# schematic.net
KiCad netlist of a schematic drawn in EAGLE
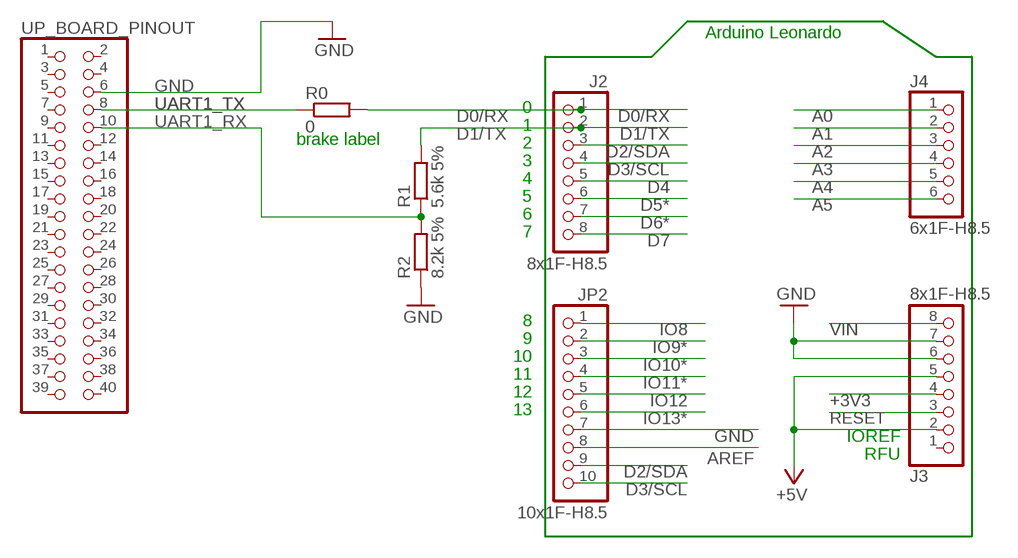
[diagram p0: schematic, sheet 1]

(export (version "E")
  (design (tool "Eeschema 10.0.6"))
  (components
    (comp (ref "J2")
      (value "8x1F-H8.5")
      (footprint "eagle-import:1X08")
      (libsource (lib "eagle-import") (part "PINHD-1X8"))
    )
    (comp (ref "J3")
      (value "8x1F-H8.5")
      (footprint "eagle-import:1X08")
      (libsource (lib "eagle-import") (part "PINHD-1X8"))
    )
    (comp (ref "J4")
      (value "6x1F-H8.5")
      (footprint "eagle-import:1X06")
      (libsource (lib "eagle-import") (part "PINHD-1X6"))
    )
    (comp (ref "JP2")
      (value "10x1F-H8.5")
      (footprint "eagle-import:1X10")
      (libsource (lib "eagle-import") (part "PINHD-1X10"))
    )
    (comp (ref "R0")
      (value "0")
      (footprint "eagle-import:0204V")
      (libsource (lib "eagle-import") (part "R-EU_0204/2V"))
    )
    (comp (ref "R1")
      (value "5.6k 5%")
      (footprint "eagle-import:0204V")
      (libsource (lib "eagle-import") (part "R-EU_0204/2V"))
    )
    (comp (ref "R2")
      (value "8.2k 5%")
      (footprint "eagle-import:0204V")
      (libsource (lib "eagle-import") (part "R-EU_0204/2V"))
    )
    (comp (ref "UP_BOARD_PINOUT")
      (value "PINHD-2X20")
      (footprint "eagle-import:2X20")
      (libsource (lib "eagle-import") (part "PINHD-2X20"))
    )
  )
  (nets
    (net (code "1") (name "+5V") (class "Default")
      (node (ref "J3") (pin "2") (pinfunction "2_2") (pintype "passive"))
      (node (ref "J3") (pin "5") (pinfunction "5_5") (pintype "passive"))
    )
    (net (code "2") (name "/+3V3") (class "Default")
      (node (ref "J3") (pin "4") (pinfunction "4_4") (pintype "passive"))
    )
    (net (code "3") (name "/A0") (class "Default")
      (node (ref "J4") (pin "1") (pinfunction "1_1") (pintype "passive"))
    )
    (net (code "4") (name "/A1") (class "Default")
      (node (ref "J4") (pin "2") (pinfunction "2_2") (pintype "passive"))
    )
    (net (code "5") (name "/A2") (class "Default")
      (node (ref "J4") (pin "3") (pinfunction "3_3") (pintype "passive"))
    )
    (net (code "6") (name "/A3") (class "Default")
      (node (ref "J4") (pin "4") (pinfunction "4_4") (pintype "passive"))
    )
    (net (code "7") (name "/A4") (class "Default")
      (node (ref "J4") (pin "5") (pinfunction "5_5") (pintype "passive"))
    )
    (net (code "8") (name "/A5") (class "Default")
      (node (ref "J4") (pin "6") (pinfunction "6_6") (pintype "passive"))
    )
    (net (code "9") (name "/AREF") (class "Default")
      (node (ref "JP2") (pin "8") (pinfunction "8_8") (pintype "passive"))
    )
    (net (code "10") (name "/D0{slash}RX") (class "Default")
      (node (ref "J2") (pin "1") (pinfunction "1_1") (pintype "passive"))
      (node (ref "R0") (pin "2") (pinfunction "2_2") (pintype "passive"))
    )
    (net (code "11") (name "/D1{slash}TX") (class "Default")
      (node (ref "J2") (pin "2") (pinfunction "2_2") (pintype "passive"))
      (node (ref "R1") (pin "2") (pinfunction "2_2") (pintype "passive"))
    )
    (net (code "12") (name "/D2{slash}SDA") (class "Default")
      (node (ref "J2") (pin "3") (pinfunction "3_3") (pintype "passive"))
      (node (ref "JP2") (pin "9") (pinfunction "9_9") (pintype "passive"))
    )
    (net (code "13") (name "/D3{slash}SCL") (class "Default")
      (node (ref "J2") (pin "4") (pinfunction "4_4") (pintype "passive"))
      (node (ref "JP2") (pin "10") (pinfunction "10_10") (pintype "passive"))
    )
    (net (code "14") (name "/D4") (class "Default")
      (node (ref "J2") (pin "5") (pinfunction "5_5") (pintype "passive"))
    )
    (net (code "15") (name "/D5*") (class "Default")
      (node (ref "J2") (pin "6") (pinfunction "6_6") (pintype "passive"))
    )
    (net (code "16") (name "/D6*") (class "Default")
      (node (ref "J2") (pin "7") (pinfunction "7_7") (pintype "passive"))
    )
    (net (code "17") (name "/D7") (class "Default")
      (node (ref "J2") (pin "8") (pinfunction "8_8") (pintype "passive"))
    )
    (net (code "18") (name "/IO8") (class "Default")
      (node (ref "JP2") (pin "1") (pinfunction "1_1") (pintype "passive"))
    )
    (net (code "19") (name "/IO9*") (class "Default")
      (node (ref "JP2") (pin "2") (pinfunction "2_2") (pintype "passive"))
    )
    (net (code "20") (name "/IO10*") (class "Default")
      (node (ref "JP2") (pin "3") (pinfunction "3_3") (pintype "passive"))
    )
    (net (code "21") (name "/IO11*") (class "Default")
      (node (ref "JP2") (pin "4") (pinfunction "4_4") (pintype "passive"))
    )
    (net (code "22") (name "/IO12") (class "Default")
      (node (ref "JP2") (pin "5") (pinfunction "5_5") (pintype "passive"))
    )
    (net (code "23") (name "/IO13*") (class "Default")
      (node (ref "JP2") (pin "6") (pinfunction "6_6") (pintype "passive"))
    )
    (net (code "24") (name "/RESET") (class "Default")
      (node (ref "J3") (pin "3") (pinfunction "3_3") (pintype "passive"))
    )
    (net (code "25") (name "/UART1_RX") (class "Default")
      (node (ref "R1") (pin "1") (pinfunction "1_1") (pintype "passive"))
      (node (ref "R2") (pin "2") (pinfunction "2_2") (pintype "passive"))
      (node (ref "UP_BOARD_PINOUT") (pin "10") (pinfunction "10_10") (pintype "passive"))
    )
    (net (code "26") (name "/UART1_TX") (class "Default")
      (node (ref "R0") (pin "1") (pinfunction "1_1") (pintype "passive"))
      (node (ref "UP_BOARD_PINOUT") (pin "8") (pinfunction "8_8") (pintype "passive"))
    )
    (net (code "27") (name "/VIN") (class "Default")
      (node (ref "J3") (pin "8") (pinfunction "8_8") (pintype "passive"))
    )
    (net (code "28") (name "GND") (class "Default")
      (node (ref "J3") (pin "6") (pinfunction "6_6") (pintype "passive"))
      (node (ref "J3") (pin "7") (pinfunction "7_7") (pintype "passive"))
      (node (ref "JP2") (pin "7") (pinfunction "7_7") (pintype "passive"))
      (node (ref "R2") (pin "1") (pinfunction "1_1") (pintype "passive"))
      (node (ref "UP_BOARD_PINOUT") (pin "6") (pinfunction "6_6") (pintype "passive"))
    )
    (net (code "29") (name "unconnected-(J3-Pad1)") (class "Default")
      (node (ref "J3") (pin "1") (pinfunction "1_1") (pintype "passive"))
    )
    (net (code "30") (name "unconnected-(UP_BOARD_PINOUT-Pad1)") (class "Default")
      (node (ref "UP_BOARD_PINOUT") (pin "1") (pinfunction "1_1") (pintype "passive"))
    )
    (net (code "31") (name "unconnected-(UP_BOARD_PINOUT-Pad2)") (class "Default")
      (node (ref "UP_BOARD_PINOUT") (pin "2") (pinfunction "2_2") (pintype "passive"))
    )
    (net (code "32") (name "unconnected-(UP_BOARD_PINOUT-Pad3)") (class "Default")
      (node (ref "UP_BOARD_PINOUT") (pin "3") (pinfunction "3_3") (pintype "passive"))
    )
    (net (code "33") (name "unconnected-(UP_BOARD_PINOUT-Pad4)") (class "Default")
      (node (ref "UP_BOARD_PINOUT") (pin "4") (pinfunction "4_4") (pintype "passive"))
    )
    (net (code "34") (name "unconnected-(UP_BOARD_PINOUT-Pad5)") (class "Default")
      (node (ref "UP_BOARD_PINOUT") (pin "5") (pinfunction "5_5") (pintype "passive"))
    )
    (net (code "35") (name "unconnected-(UP_BOARD_PINOUT-Pad7)") (class "Default")
      (node (ref "UP_BOARD_PINOUT") (pin "7") (pinfunction "7_7") (pintype "passive"))
    )
    (net (code "36") (name "unconnected-(UP_BOARD_PINOUT-Pad9)") (class "Default")
      (node (ref "UP_BOARD_PINOUT") (pin "9") (pinfunction "9_9") (pintype "passive"))
    )
    (net (code "37") (name "unconnected-(UP_BOARD_PINOUT-Pad11)") (class "Default")
      (node (ref "UP_BOARD_PINOUT") (pin "11") (pinfunction "11_11") (pintype "passive"))
    )
    (net (code "38") (name "unconnected-(UP_BOARD_PINOUT-Pad12)") (class "Default")
      (node (ref "UP_BOARD_PINOUT") (pin "12") (pinfunction "12_12") (pintype "passive"))
    )
    (net (code "39") (name "unconnected-(UP_BOARD_PINOUT-Pad13)") (class "Default")
      (node (ref "UP_BOARD_PINOUT") (pin "13") (pinfunction "13_13") (pintype "passive"))
    )
    (net (code "40") (name "unconnected-(UP_BOARD_PINOUT-Pad14)") (class "Default")
      (node (ref "UP_BOARD_PINOUT") (pin "14") (pinfunction "14_14") (pintype "passive"))
    )
    (net (code "41") (name "unconnected-(UP_BOARD_PINOUT-Pad15)") (class "Default")
      (node (ref "UP_BOARD_PINOUT") (pin "15") (pinfunction "15_15") (pintype "passive"))
    )
    (net (code "42") (name "unconnected-(UP_BOARD_PINOUT-Pad16)") (class "Default")
      (node (ref "UP_BOARD_PINOUT") (pin "16") (pinfunction "16_16") (pintype "passive"))
    )
    (net (code "43") (name "unconnected-(UP_BOARD_PINOUT-Pad17)") (class "Default")
      (node (ref "UP_BOARD_PINOUT") (pin "17") (pinfunction "17_17") (pintype "passive"))
    )
    (net (code "44") (name "unconnected-(UP_BOARD_PINOUT-Pad18)") (class "Default")
      (node (ref "UP_BOARD_PINOUT") (pin "18") (pinfunction "18_18") (pintype "passive"))
    )
    (net (code "45") (name "unconnected-(UP_BOARD_PINOUT-Pad19)") (class "Default")
      (node (ref "UP_BOARD_PINOUT") (pin "19") (pinfunction "19_19") (pintype "passive"))
    )
    (net (code "46") (name "unconnected-(UP_BOARD_PINOUT-Pad20)") (class "Default")
      (node (ref "UP_BOARD_PINOUT") (pin "20") (pinfunction "20_20") (pintype "passive"))
    )
    (net (code "47") (name "unconnected-(UP_BOARD_PINOUT-Pad21)") (class "Default")
      (node (ref "UP_BOARD_PINOUT") (pin "21") (pinfunction "21_21") (pintype "passive"))
    )
    (net (code "48") (name "unconnected-(UP_BOARD_PINOUT-Pad22)") (class "Default")
      (node (ref "UP_BOARD_PINOUT") (pin "22") (pinfunction "22_22") (pintype "passive"))
    )
    (net (code "49") (name "unconnected-(UP_BOARD_PINOUT-Pad23)") (class "Default")
      (node (ref "UP_BOARD_PINOUT") (pin "23") (pinfunction "23_23") (pintype "passive"))
    )
    (net (code "50") (name "unconnected-(UP_BOARD_PINOUT-Pad24)") (class "Default")
      (node (ref "UP_BOARD_PINOUT") (pin "24") (pinfunction "24_24") (pintype "passive"))
    )
    (net (code "51") (name "unconnected-(UP_BOARD_PINOUT-Pad25)") (class "Default")
      (node (ref "UP_BOARD_PINOUT") (pin "25") (pinfunction "25_25") (pintype "passive"))
    )
    (net (code "52") (name "unconnected-(UP_BOARD_PINOUT-Pad26)") (class "Default")
      (node (ref "UP_BOARD_PINOUT") (pin "26") (pinfunction "26_26") (pintype "passive"))
    )
    (net (code "53") (name "unconnected-(UP_BOARD_PINOUT-Pad27)") (class "Default")
      (node (ref "UP_BOARD_PINOUT") (pin "27") (pinfunction "27_27") (pintype "passive"))
    )
    (net (code "54") (name "unconnected-(UP_BOARD_PINOUT-Pad28)") (class "Default")
      (node (ref "UP_BOARD_PINOUT") (pin "28") (pinfunction "28_28") (pintype "passive"))
    )
    (net (code "55") (name "unconnected-(UP_BOARD_PINOUT-Pad29)") (class "Default")
      (node (ref "UP_BOARD_PINOUT") (pin "29") (pinfunction "29_29") (pintype "passive"))
    )
    (net (code "56") (name "unconnected-(UP_BOARD_PINOUT-Pad30)") (class "Default")
      (node (ref "UP_BOARD_PINOUT") (pin "30") (pinfunction "30_30") (pintype "passive"))
    )
    (net (code "57") (name "unconnected-(UP_BOARD_PINOUT-Pad31)") (class "Default")
      (node (ref "UP_BOARD_PINOUT") (pin "31") (pinfunction "31_31") (pintype "passive"))
    )
    (net (code "58") (name "unconnected-(UP_BOARD_PINOUT-Pad32)") (class "Default")
      (node (ref "UP_BOARD_PINOUT") (pin "32") (pinfunction "32_32") (pintype "passive"))
    )
    (net (code "59") (name "unconnected-(UP_BOARD_PINOUT-Pad33)") (class "Default")
      (node (ref "UP_BOARD_PINOUT") (pin "33") (pinfunction "33_33") (pintype "passive"))
    )
    (net (code "60") (name "unconnected-(UP_BOARD_PINOUT-Pad34)") (class "Default")
      (node (ref "UP_BOARD_PINOUT") (pin "34") (pinfunction "34_34") (pintype "passive"))
    )
    (net (code "61") (name "unconnected-(UP_BOARD_PINOUT-Pad35)") (class "Default")
      (node (ref "UP_BOARD_PINOUT") (pin "35") (pinfunction "35_35") (pintype "passive"))
    )
    (net (code "62") (name "unconnected-(UP_BOARD_PINOUT-Pad36)") (class "Default")
      (node (ref "UP_BOARD_PINOUT") (pin "36") (pinfunction "36_36") (pintype "passive"))
    )
    (net (code "63") (name "unconnected-(UP_BOARD_PINOUT-Pad37)") (class "Default")
      (node (ref "UP_BOARD_PINOUT") (pin "37") (pinfunction "37_37") (pintype "passive"))
    )
    (net (code "64") (name "unconnected-(UP_BOARD_PINOUT-Pad38)") (class "Default")
      (node (ref "UP_BOARD_PINOUT") (pin "38") (pinfunction "38_38") (pintype "passive"))
    )
    (net (code "65") (name "unconnected-(UP_BOARD_PINOUT-Pad39)") (class "Default")
      (node (ref "UP_BOARD_PINOUT") (pin "39") (pinfunction "39_39") (pintype "passive"))
    )
    (net (code "66") (name "unconnected-(UP_BOARD_PINOUT-Pad40)") (class "Default")
      (node (ref "UP_BOARD_PINOUT") (pin "40") (pinfunction "40_40") (pintype "passive"))
    )
  )
)
